# clock.net
KiCad netlist of a schematic drawn in Altium Designer
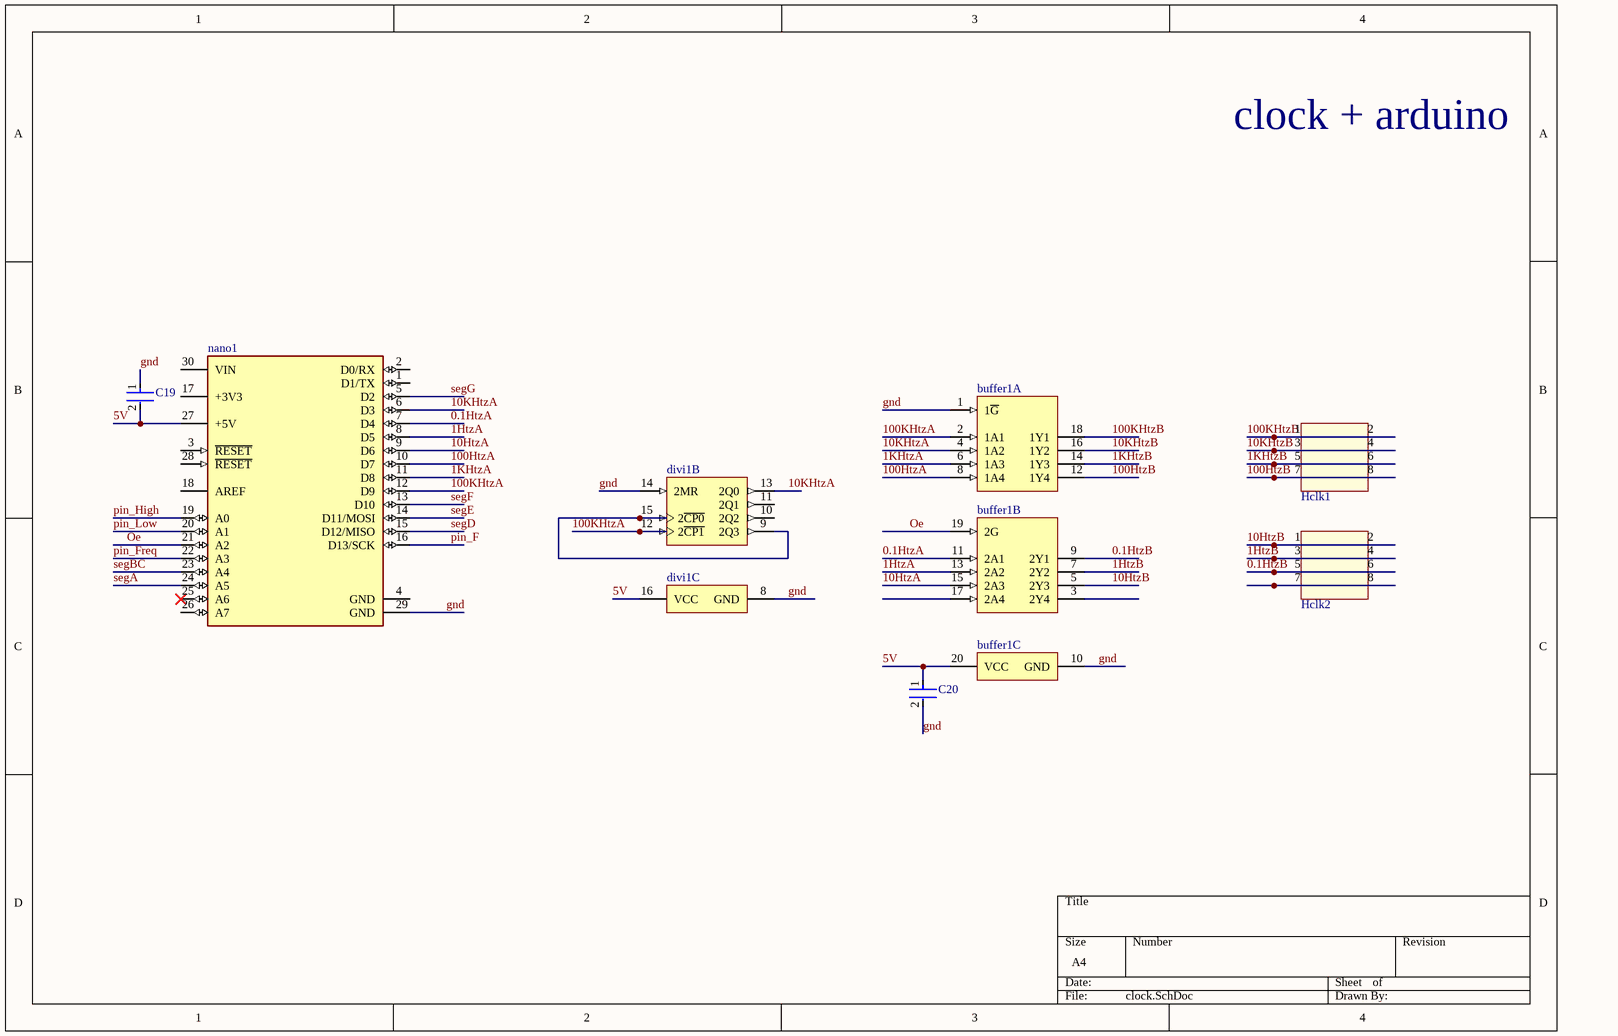
[diagram p0: clock.SchDoc]

(export (version "E")
  (design (tool "Eeschema 10.0.6"))
  (components
    (comp (ref "buffer1")
      (value "SN74LS241N")
      (footprint "N0020A")
      (description "Octal Buffers And Line Drivers With 3-State Outputs, N0020A, TUBE")
      (fields
        (field (name "GENERIC PART NUMBER") "SN74LS241")
        (field (name "MANUFACTURER") "Texas Instruments")
      )
      (libsource (lib "Altium Content Vault") (part "TI-SN74LS_74S241-20"))
    )
    (comp (ref "C19")
      (value "RCER71H335K3K1H03B")
      (footprint "FP-RCE3M1-MFG")
      (description "Cap Ceramic 3.3uF 50V X7R ±10% Radial 5mm +125°C Automotive Ammo Pack")
      (fields (field (name "TOLERANCE") "10%"))
      (libsource (lib "Altium Content Vault") (part "02cd4be3c70576c341d710602a673aa"))
    )
    (comp (ref "C20")
      (value "RCER71H335K3K1H03B")
      (footprint "FP-RCE3M1-MFG")
      (description "Cap Ceramic 3.3uF 50V X7R ±10% Radial 5mm +125°C Automotive Ammo Pack")
      (fields (field (name "TOLERANCE") "10%"))
      (libsource (lib "Altium Content Vault") (part "02cd4be3c70576c341d710602a673aa"))
    )
    (comp (ref "divi1")
      (value "CD74HC390E")
      (footprint "N0016A")
      (description "High Speed CMOS Logic Dual Decade Ripple Counters, N0016A, TUBE")
      (fields
        (field (name "GENERIC PART NUMBER") "CD74HC390")
        (field (name "MANUFACTURER") "Texas Instruments")
      )
      (libsource (lib "Altium Content Vault") (part "TI-CDX4HCX390-16"))
    )
    (comp (ref "Hclk1")
      (value "header 2x4")
      (footprint "header 2x4")
      (description "header male 2x4")
      (libsource (lib "Schlib1") (part "header 2x4"))
    )
    (comp (ref "Hclk2")
      (value "header 2x4")
      (footprint "header 2x4")
      (description "header male 2x4")
      (libsource (lib "Schlib1") (part "header 2x4"))
    )
    (comp (ref "nano1")
      (value "A000005")
      (footprint "FP-A000005-MFG")
      (description "ARDUINO NANO ATMEGA328 EVAL BRD")
      (libsource (lib "Altium Content Vault") (part "d190c066e99afd1c6882cf92e11b2cc"))
    )
  )
  (nets
    (net (code "1") (name "/0.1HtzA") (class "Default")
      (node (ref "buffer1") (pin "11") (pinfunction "2A1_11") (pintype "input"))
      (node (ref "nano1") (pin "7") (pinfunction "D4_7") (pintype "bidirectional"))
    )
    (net (code "2") (name "/0.1HtzB") (class "Default")
      (node (ref "Hclk2") (pin "5") (pinfunction "5_5") (pintype "passive"))
      (node (ref "Hclk2") (pin "6") (pinfunction "6_6") (pintype "passive"))
      (node (ref "buffer1") (pin "9") (pinfunction "2Y1_9") (pintype "tri_state"))
    )
    (net (code "3") (name "/1HtzA") (class "Default")
      (node (ref "buffer1") (pin "13") (pinfunction "2A2_13") (pintype "input"))
      (node (ref "nano1") (pin "8") (pinfunction "D5_8") (pintype "bidirectional"))
    )
    (net (code "4") (name "/1HtzB") (class "Default")
      (node (ref "Hclk2") (pin "3") (pinfunction "3_3") (pintype "passive"))
      (node (ref "Hclk2") (pin "4") (pinfunction "4_4") (pintype "passive"))
      (node (ref "buffer1") (pin "7") (pinfunction "2Y2_7") (pintype "tri_state"))
    )
    (net (code "5") (name "/1KHtzA") (class "Default")
      (node (ref "buffer1") (pin "6") (pinfunction "1A3_6") (pintype "input"))
      (node (ref "nano1") (pin "11") (pinfunction "D8_11") (pintype "bidirectional"))
    )
    (net (code "6") (name "/1KHtzB") (class "Default")
      (node (ref "Hclk1") (pin "5") (pinfunction "5_5") (pintype "passive"))
      (node (ref "Hclk1") (pin "6") (pinfunction "6_6") (pintype "passive"))
      (node (ref "buffer1") (pin "14") (pinfunction "1Y3_14") (pintype "tri_state"))
    )
    (net (code "7") (name "/5V") (class "Default")
      (node (ref "C19") (pin "2") (pinfunction "2_2") (pintype "passive"))
      (node (ref "C20") (pin "1") (pinfunction "1_1") (pintype "passive"))
      (node (ref "buffer1") (pin "20") (pinfunction "VCC_20") (pintype "power_in"))
      (node (ref "divi1") (pin "16") (pinfunction "VCC_16") (pintype "power_in"))
      (node (ref "nano1") (pin "27") (pinfunction "+5V_27") (pintype "power_in"))
    )
    (net (code "8") (name "/10HtzA") (class "Default")
      (node (ref "buffer1") (pin "15") (pinfunction "2A3_15") (pintype "input"))
      (node (ref "nano1") (pin "9") (pinfunction "D6_9") (pintype "bidirectional"))
    )
    (net (code "9") (name "/10HtzB") (class "Default")
      (node (ref "Hclk2") (pin "1") (pinfunction "1_1") (pintype "passive"))
      (node (ref "Hclk2") (pin "2") (pinfunction "2_2") (pintype "passive"))
      (node (ref "buffer1") (pin "5") (pinfunction "2Y3_5") (pintype "tri_state"))
    )
    (net (code "10") (name "/10KHtzA") (class "Default")
      (node (ref "buffer1") (pin "4") (pinfunction "1A2_4") (pintype "input"))
      (node (ref "divi1") (pin "13") (pinfunction "2Q0_13") (pintype "output"))
      (node (ref "nano1") (pin "6") (pinfunction "D3_6") (pintype "bidirectional"))
    )
    (net (code "11") (name "/10KHtzB") (class "Default")
      (node (ref "Hclk1") (pin "3") (pinfunction "3_3") (pintype "passive"))
      (node (ref "Hclk1") (pin "4") (pinfunction "4_4") (pintype "passive"))
      (node (ref "buffer1") (pin "16") (pinfunction "1Y2_16") (pintype "tri_state"))
    )
    (net (code "12") (name "/100HtzA") (class "Default")
      (node (ref "buffer1") (pin "8") (pinfunction "1A4_8") (pintype "input"))
      (node (ref "nano1") (pin "10") (pinfunction "D7_10") (pintype "bidirectional"))
    )
    (net (code "13") (name "/100HtzB") (class "Default")
      (node (ref "Hclk1") (pin "7") (pinfunction "7_7") (pintype "passive"))
      (node (ref "Hclk1") (pin "8") (pinfunction "8_8") (pintype "passive"))
      (node (ref "buffer1") (pin "12") (pinfunction "1Y4_12") (pintype "tri_state"))
    )
    (net (code "14") (name "/100KHtzA") (class "Default")
      (node (ref "buffer1") (pin "2") (pinfunction "1A1_2") (pintype "input"))
      (node (ref "divi1") (pin "12") (pinfunction "2~{CP1}_12") (pintype "input"))
      (node (ref "nano1") (pin "12") (pinfunction "D9_12") (pintype "bidirectional"))
    )
    (net (code "15") (name "/100KHtzB") (class "Default")
      (node (ref "Hclk1") (pin "1") (pinfunction "1_1") (pintype "passive"))
      (node (ref "Hclk1") (pin "2") (pinfunction "2_2") (pintype "passive"))
      (node (ref "buffer1") (pin "18") (pinfunction "1Y1_18") (pintype "tri_state"))
    )
    (net (code "16") (name "/Oe") (class "Default")
      (node (ref "buffer1") (pin "19") (pinfunction "2G_19") (pintype "input"))
      (node (ref "nano1") (pin "21") (pinfunction "A2_21") (pintype "bidirectional"))
    )
    (net (code "17") (name "/gnd") (class "Default")
      (node (ref "C19") (pin "1") (pinfunction "1_1") (pintype "passive"))
      (node (ref "C20") (pin "2") (pinfunction "2_2") (pintype "passive"))
      (node (ref "buffer1") (pin "1") (pinfunction "1~{G}_1") (pintype "input"))
      (node (ref "buffer1") (pin "10") (pinfunction "GND_10") (pintype "power_in"))
      (node (ref "divi1") (pin "14") (pinfunction "2MR_14") (pintype "input"))
      (node (ref "divi1") (pin "8") (pinfunction "GND_8") (pintype "power_in"))
      (node (ref "nano1") (pin "29") (pinfunction "GND_29") (pintype "power_in"))
    )
    (net (code "18") (name "/pin_F") (class "Default")
      (node (ref "nano1") (pin "16") (pinfunction "D13/SCK_16") (pintype "bidirectional"))
    )
    (net (code "19") (name "/pin_Freq") (class "Default")
      (node (ref "nano1") (pin "22") (pinfunction "A3_22") (pintype "bidirectional"))
    )
    (net (code "20") (name "/pin_High") (class "Default")
      (node (ref "nano1") (pin "19") (pinfunction "A0_19") (pintype "bidirectional"))
    )
    (net (code "21") (name "/pin_Low") (class "Default")
      (node (ref "nano1") (pin "20") (pinfunction "A1_20") (pintype "bidirectional"))
    )
    (net (code "22") (name "/segA") (class "Default")
      (node (ref "nano1") (pin "24") (pinfunction "A5_24") (pintype "bidirectional"))
    )
    (net (code "23") (name "/segBC") (class "Default")
      (node (ref "nano1") (pin "23") (pinfunction "A4_23") (pintype "bidirectional"))
    )
    (net (code "24") (name "/segD") (class "Default")
      (node (ref "nano1") (pin "15") (pinfunction "D12/MISO_15") (pintype "bidirectional"))
    )
    (net (code "25") (name "/segE") (class "Default")
      (node (ref "nano1") (pin "14") (pinfunction "D11/MOSI_14") (pintype "bidirectional"))
    )
    (net (code "26") (name "/segF") (class "Default")
      (node (ref "nano1") (pin "13") (pinfunction "D10_13") (pintype "bidirectional"))
    )
    (net (code "27") (name "/segG") (class "Default")
      (node (ref "nano1") (pin "5") (pinfunction "D2_5") (pintype "bidirectional"))
    )
    (net (code "28") (name "Net-(Hclk2-Pad7)") (class "Default")
      (node (ref "Hclk2") (pin "7") (pinfunction "7_7") (pintype "passive"))
      (node (ref "Hclk2") (pin "8") (pinfunction "8_8") (pintype "passive"))
    )
    (net (code "29") (name "Net-(divi1B-2Q3)") (class "Default")
      (node (ref "divi1") (pin "15") (pinfunction "2~{CP0}_15") (pintype "input"))
      (node (ref "divi1") (pin "9") (pinfunction "2Q3_9") (pintype "output"))
    )
    (net (code "30") (name "unconnected-(buffer1B-2A4-Pad17)") (class "Default")
      (node (ref "buffer1") (pin "17") (pinfunction "2A4_17") (pintype "input"))
    )
    (net (code "31") (name "unconnected-(buffer1B-2Y4-Pad3)") (class "Default")
      (node (ref "buffer1") (pin "3") (pinfunction "2Y4_3") (pintype "tri_state"))
    )
    (net (code "32") (name "unconnected-(divi1B-2Q1-Pad11)") (class "Default")
      (node (ref "divi1") (pin "11") (pinfunction "2Q1_11") (pintype "output"))
    )
    (net (code "33") (name "unconnected-(divi1B-2Q2-Pad10)") (class "Default")
      (node (ref "divi1") (pin "10") (pinfunction "2Q2_10") (pintype "output"))
    )
    (net (code "34") (name "unconnected-(nano1-+3V3-Pad17)") (class "Default")
      (node (ref "nano1") (pin "17") (pinfunction "+3V3_17") (pintype "power_in"))
    )
    (net (code "35") (name "unconnected-(nano1-A6-Pad25)") (class "Default")
      (node (ref "nano1") (pin "25") (pinfunction "A6_25") (pintype "bidirectional+no_connect"))
    )
    (net (code "36") (name "unconnected-(nano1-A7-Pad26)") (class "Default")
      (node (ref "nano1") (pin "26") (pinfunction "A7_26") (pintype "bidirectional"))
    )
    (net (code "37") (name "unconnected-(nano1-AREF-Pad18)") (class "Default")
      (node (ref "nano1") (pin "18") (pinfunction "AREF_18") (pintype "passive"))
    )
    (net (code "38") (name "unconnected-(nano1-D0{slash}RX-Pad2)") (class "Default")
      (node (ref "nano1") (pin "2") (pinfunction "D0/RX_2") (pintype "bidirectional"))
    )
    (net (code "39") (name "unconnected-(nano1-D1{slash}TX-Pad1)") (class "Default")
      (node (ref "nano1") (pin "1") (pinfunction "D1/TX_1") (pintype "bidirectional"))
    )
    (net (code "40") (name "unconnected-(nano1-GND-Pad4)") (class "Default")
      (node (ref "nano1") (pin "4") (pinfunction "GND_4") (pintype "power_in"))
    )
    (net (code "41") (name "unconnected-(nano1-VIN-Pad30)") (class "Default")
      (node (ref "nano1") (pin "30") (pinfunction "VIN_30") (pintype "power_in"))
    )
    (net (code "42") (name "unconnected-(nano1-~{RESET}-Pad3)") (class "Default")
      (node (ref "nano1") (pin "3") (pinfunction "~{RESET}_3") (pintype "input"))
    )
    (net (code "43") (name "unconnected-(nano1-~{RESET}-Pad28)") (class "Default")
      (node (ref "nano1") (pin "28") (pinfunction "~{RESET}_28") (pintype "input"))
    )
  )
)
